# 03_BATTERY_MANAGEMENT.net
KiCad netlist of a schematic drawn in Altium Designer
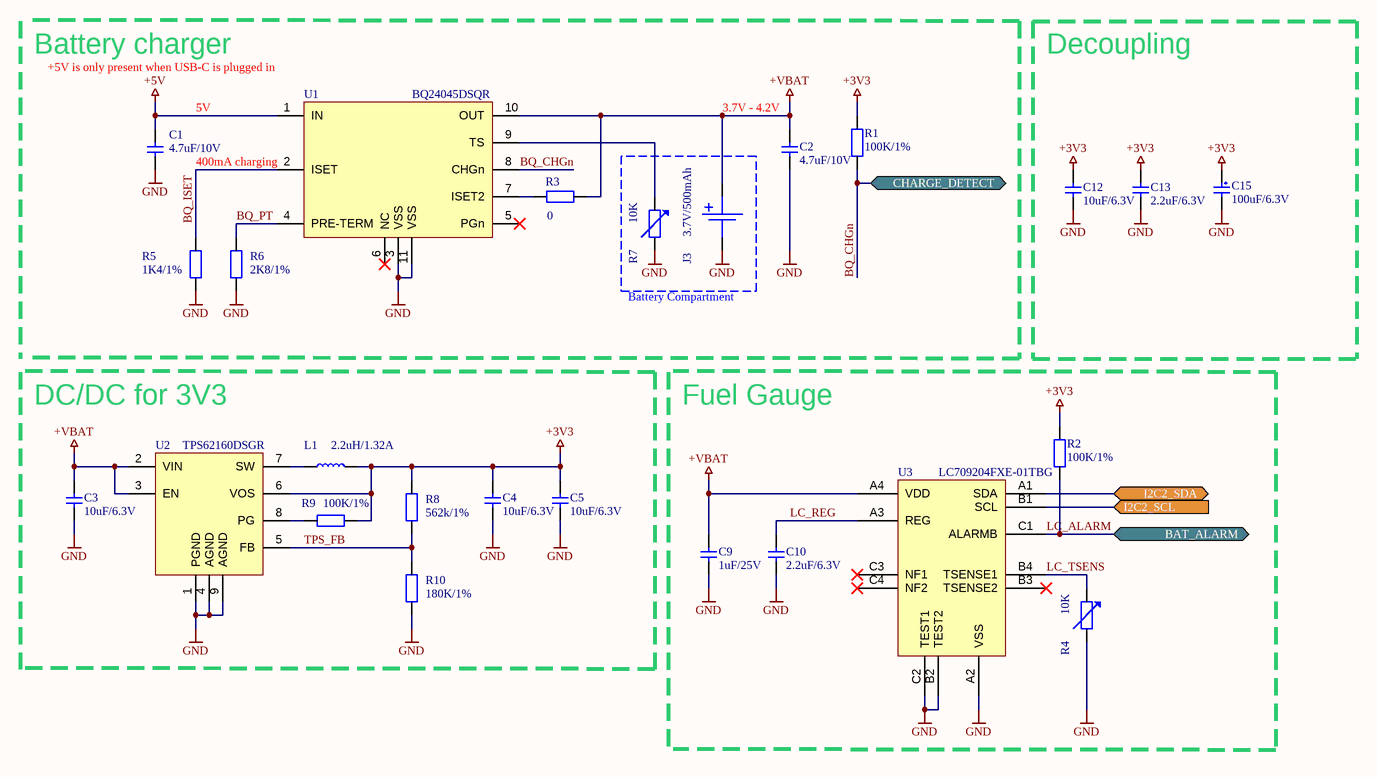
[diagram p0: 03 BATTERY MANAGEMENT.SchDoc]

(export (version "E")
  (design (tool "Eeschema 10.0.6"))
  (components
    (comp (ref "C1")
      (value "4.7uF/10V")
      (footprint "CAPC1005X06N")
      (description "10V 4.7uF X5R ±20% 0402  Multilayer Ceramic Capacitors MLCC - SMD/SMT ROHS")
      (fields
        (field (name "MANUFACTURER") "Samsung Electro-Mechanics")
        (field (name "MFR_PART_NUMBER") "CL05A475MP5NRNC")
      )
      (libsource (lib "altium_symbol") (part "CL05A475MP5NRNC"))
    )
    (comp (ref "C2")
      (value "4.7uF/10V")
      (footprint "CAPC1005X06N")
      (description "10V 4.7uF X5R ±20% 0402  Multilayer Ceramic Capacitors MLCC - SMD/SMT ROHS")
      (fields
        (field (name "MANUFACTURER") "Samsung Electro-Mechanics")
        (field (name "MFR_PART_NUMBER") "CL05A475MP5NRNC")
      )
      (libsource (lib "altium_symbol") (part "CL05A475MP5NRNC"))
    )
    (comp (ref "C3")
      (value "10uF/6.3V")
      (footprint "CAPC1005X06N")
      (description "6.3V 10uF X5R ±20% 0402  Multilayer Ceramic Capacitors MLCC - SMD/SMT ROHS")
      (fields
        (field (name "MANUFACTURER") "Samsung Electro-Mechanics")
        (field (name "MFR_PART_NUMBER") "CL05A106MQ5NUNC")
      )
      (libsource (lib "altium_symbol") (part "CL05A106MQ5NUNC"))
    )
    (comp (ref "C4")
      (value "10uF/6.3V")
      (footprint "CAPC1005X06N")
      (description "6.3V 10uF X5R ±20% 0402  Multilayer Ceramic Capacitors MLCC - SMD/SMT ROHS")
      (fields
        (field (name "MANUFACTURER") "Samsung Electro-Mechanics")
        (field (name "MFR_PART_NUMBER") "CL05A106MQ5NUNC")
      )
      (libsource (lib "altium_symbol") (part "CL05A106MQ5NUNC"))
    )
    (comp (ref "C5")
      (value "10uF/6.3V")
      (footprint "CAPC1005X06N")
      (description "6.3V 10uF X5R ±20% 0402  Multilayer Ceramic Capacitors MLCC - SMD/SMT ROHS")
      (fields
        (field (name "MANUFACTURER") "Samsung Electro-Mechanics")
        (field (name "MFR_PART_NUMBER") "CL05A106MQ5NUNC")
      )
      (libsource (lib "altium_symbol") (part "CL05A106MQ5NUNC"))
    )
    (comp (ref "C9")
      (value "1uF/25V")
      (footprint "CAPC1005X06N")
      (description "25V 1uF X5R ±10% 0402  Multilayer Ceramic Capacitors MLCC - SMD/SMT ROHS")
      (fields
        (field (name "MANUFACTURER") "Samsung Electro-Mechanics")
        (field (name "MFR_PART_NUMBER") "CL05A105KA5NQNC")
      )
      (libsource (lib "altium_symbol") (part "CL05A105KA5NQNC"))
    )
    (comp (ref "C10")
      (value "2.2uF/6.3V")
      (footprint "CAPC1005X06N")
      (description "6.3V 2.2uF X5R ±20% 0402  Multilayer Ceramic Capacitors MLCC - SMD/SMT ROHS")
      (fields
        (field (name "MANUFACTURER") "Samsung Electro-Mechanics")
        (field (name "MFR_PART_NUMBER") "CL05A225MQ5NSNC")
      )
      (libsource (lib "altium_symbol") (part "CL05A225MQ5NSNC"))
    )
    (comp (ref "C12")
      (value "10uF/6.3V")
      (footprint "CAPC1005X06N")
      (description "6.3V 10uF X5R ±20% 0402  Multilayer Ceramic Capacitors MLCC - SMD/SMT ROHS")
      (fields
        (field (name "MANUFACTURER") "Samsung Electro-Mechanics")
        (field (name "MFR_PART_NUMBER") "CL05A106MQ5NUNC")
      )
      (libsource (lib "altium_symbol") (part "CL05A106MQ5NUNC"))
    )
    (comp (ref "C13")
      (value "2.2uF/6.3V")
      (footprint "CAPC1005X06N")
      (description "6.3V 2.2uF X5R ±20% 0402  Multilayer Ceramic Capacitors MLCC - SMD/SMT ROHS")
      (fields
        (field (name "MANUFACTURER") "Samsung Electro-Mechanics")
        (field (name "MFR_PART_NUMBER") "CL05A225MQ5NSNC")
      )
      (libsource (lib "altium_symbol") (part "CL05A225MQ5NSNC"))
    )
    (comp (ref "C15")
      (value "100uF/6.3V")
      (footprint "CAPMP3528X21N")
      (description "100uF 6.3V -55℃~+125℃ 1.7Ω@100kHz ±10% CASE-B_3528 Tantalum Capacitors ROHS")
      (fields (field (name "MANUFACTURER") "Kyocera AVX") (field (name "MFR_PART_NUMBER") "TAJB107K006RNJ"))
      (libsource (lib "altium_symbol") (part "TAJB107K006RNJ"))
    )
    (comp (ref "J3")
      (value "3.7V/500mAh")
      (footprint "BATTERY_SMD_CONN")
      (description "SMD_Connector_2Pole")
      (libsource (lib "altium_symbol") (part "SMD_Connector_2Pole"))
    )
    (comp (ref "L1")
      (value "2.2uH/1.32A")
      (footprint "INDP4040X12N")
      (description "1.32A 2.2uH ±20% 104mΩ SMD  Power Inductors ROHS")
      (fields
        (field (name "MANUFACTURER") "cjiang(Changjiang Microelectronics Tech)")
        (field (name "MFR_PART_NUMBER") "FNR4012S2R2MT")
      )
      (libsource (lib "altium_symbol") (part "FNR4012S2R2MT"))
    )
    (comp (ref "R1")
      (value "100K/1%")
      (footprint "RESC1005X04N")
      (fields
        (field (name "MANUFACTURER") "UNI-ROYAL(Uniroyal Elec)")
        (field (name "MFR_PART_NUMBER") "0402WGF1003TCE")
      )
      (libsource (lib "altium_symbol") (part "0402WGF1003TCE"))
    )
    (comp (ref "R2")
      (value "100K/1%")
      (footprint "RESC1005X04N")
      (fields
        (field (name "MANUFACTURER") "UNI-ROYAL(Uniroyal Elec)")
        (field (name "MFR_PART_NUMBER") "0402WGF1003TCE")
      )
      (libsource (lib "altium_symbol") (part "0402WGF1003TCE"))
    )
    (comp (ref "R3")
      (value "0")
      (footprint "RESC1005X04N")
      (fields
        (field (name "MANUFACTURER") "UNI-ROYAL(Uniroyal Elec)")
        (field (name "MFR_PART_NUMBER") "0402WGF0000TCE")
      )
      (libsource (lib "altium_symbol") (part "0402WGF0000TCE"))
    )
    (comp (ref "R4")
      (value "10K")
      (footprint "RESC1005X04N")
      (description "10kΩ -55℃~+125℃ 0.33mA 100mW ±1% 3950K ±1% 0603  NTC Thermistors ROHS")
      (fields (field (name "MANUFACTURER") "Sunlord") (field (name "MFR_PART_NUMBER") "SDNT1608X103F3950FTF"))
      (libsource (lib "altium_symbol") (part "SDNT1608X103F3950FTF"))
    )
    (comp (ref "R5")
      (value "1K4/1%")
      (footprint "RESC1005X04N")
      (fields
        (field (name "MANUFACTURER") "UNI-ROYAL(Uniroyal Elec)")
        (field (name "MFR_PART_NUMBER") "0402WGF1401TCE")
      )
      (libsource (lib "altium_symbol") (part "0402WGF1401TCE"))
    )
    (comp (ref "R6")
      (value "2K8/1%")
      (footprint "RESC1005X04N")
      (description "62.5mW 50V ±100ppm/℃ ±1% -55℃~+155℃ 2.8kΩ 0402  Chip Resistor - Surface Mount ROHS")
      (fields
        (field (name "MANUFACTURER") "Walsin Tech Corp")
        (field (name "MFR_PART_NUMBER") "WR04X2801FTL")
      )
      (libsource (lib "altium_symbol") (part "WR04X2801FTL"))
    )
    (comp (ref "R7")
      (value "10K")
      (footprint "RESC1005X04N")
      (description "10kΩ -55℃~+125℃ 0.33mA 100mW ±1% 3950K ±1% 0603  NTC Thermistors ROHS")
      (fields (field (name "MANUFACTURER") "Sunlord") (field (name "MFR_PART_NUMBER") "SDNT1608X103F3950FTF"))
      (libsource (lib "altium_symbol") (part "SDNT1608X103F3950FTF"))
    )
    (comp (ref "R8")
      (value "562k/1%")
      (footprint "RESC1005X04N")
      (fields
        (field (name "MANUFACTURER") "UNI-ROYAL(Uniroyal Elec)")
        (field (name "MFR_PART_NUMBER") "0402WGF5623TCE")
      )
      (libsource (lib "altium_symbol") (part "0402WGF5623TCE"))
    )
    (comp (ref "R9")
      (value "100K/1%")
      (footprint "RESC1005X04N")
      (fields
        (field (name "MANUFACTURER") "UNI-ROYAL(Uniroyal Elec)")
        (field (name "MFR_PART_NUMBER") "0402WGF1003TCE")
      )
      (libsource (lib "altium_symbol") (part "0402WGF1003TCE"))
    )
    (comp (ref "R10")
      (value "180K/1%")
      (footprint "RESC1005X04N")
      (fields
        (field (name "MANUFACTURER") "UNI-ROYAL(Uniroyal Elec)")
        (field (name "MFR_PART_NUMBER") "0402WGF1803TCE")
      )
      (libsource (lib "altium_symbol") (part "0402WGF1803TCE"))
    )
    (comp (ref "U1")
      (value "BQ24045DSQR")
      (footprint "SON40P200X80_HS-11N")
      (description "WSON-10  Battery Management ICs ROHS")
      (fields (field (name "MANUFACTURER") "Texas Instruments"))
      (libsource (lib "altium_symbol") (part "BQ24045DSQR"))
    )
    (comp (ref "U2")
      (value "TPS62160DSGR")
      (footprint "SON50P200X80_HS-9N")
      (description "Step-down type WSON-8  DC-DC Converters ROHS")
      (fields (field (name "MANUFACTURER") "Texas Instruments"))
      (libsource (lib "altium_symbol") (part "TPS62160DSGR"))
    )
    (comp (ref "U3")
      (value "LC709204FXE-01TBG")
      (footprint "BGA12C40P4X3_191X148X51")
      (description "WLCSP12(1.48x1.91x0.51)  Battery Management ICs ROHS")
      (fields (field (name "MANUFACTURER") "onsemi"))
      (libsource (lib "altium_symbol") (part "LC709204FXE-01TBG"))
    )
  )
  (nets
    (net (code "1") (name "+3V3") (class "Default")
      (node (ref "C12") (pin "2") (pinfunction "2_2") (pintype "passive"))
      (node (ref "C13") (pin "2") (pinfunction "2_2") (pintype "passive"))
      (node (ref "C15") (pin "1") (pinfunction "1_1") (pintype "passive"))
      (node (ref "C4") (pin "2") (pinfunction "2_2") (pintype "passive"))
      (node (ref "C5") (pin "2") (pinfunction "2_2") (pintype "passive"))
      (node (ref "L1") (pin "2") (pinfunction "2_2") (pintype "passive"))
      (node (ref "R1") (pin "1") (pinfunction "1_1") (pintype "passive"))
      (node (ref "R2") (pin "1") (pinfunction "1_1") (pintype "passive"))
      (node (ref "R8") (pin "2") (pinfunction "2_2") (pintype "passive"))
      (node (ref "R9") (pin "1") (pinfunction "1_1") (pintype "passive"))
      (node (ref "U2") (pin "6") (pinfunction "VOS_6") (pintype "passive"))
    )
    (net (code "2") (name "+5V") (class "Default")
      (node (ref "C1") (pin "2") (pinfunction "2_2") (pintype "passive"))
      (node (ref "U1") (pin "1") (pinfunction "IN_1") (pintype "passive"))
    )
    (net (code "3") (name "+VBAT") (class "Default")
      (node (ref "C2") (pin "2") (pinfunction "2_2") (pintype "passive"))
      (node (ref "C3") (pin "2") (pinfunction "2_2") (pintype "passive"))
      (node (ref "C9") (pin "2") (pinfunction "2_2") (pintype "passive"))
      (node (ref "J3") (pin "1") (pinfunction "+_1") (pintype "passive"))
      (node (ref "R3") (pin "2") (pinfunction "2_2") (pintype "passive"))
      (node (ref "U1") (pin "10") (pinfunction "OUT_10") (pintype "passive"))
      (node (ref "U2") (pin "2") (pinfunction "VIN_2") (pintype "passive"))
      (node (ref "U2") (pin "3") (pinfunction "EN_3") (pintype "passive"))
      (node (ref "U3") (pin "A4") (pinfunction "VDD_A4") (pintype "passive"))
    )
    (net (code "4") (name "/BQ_CHGn") (class "Default")
      (node (ref "R1") (pin "2") (pinfunction "2_2") (pintype "passive"))
      (node (ref "U1") (pin "8") (pinfunction "CHGn_8") (pintype "passive"))
    )
    (net (code "5") (name "/BQ_ISET") (class "Default")
      (node (ref "R5") (pin "2") (pinfunction "2_2") (pintype "passive"))
      (node (ref "U1") (pin "2") (pinfunction "ISET_2") (pintype "passive"))
    )
    (net (code "6") (name "/BQ_PT") (class "Default")
      (node (ref "R6") (pin "2") (pinfunction "2_2") (pintype "passive"))
      (node (ref "U1") (pin "4") (pinfunction "PRE-TERM_4") (pintype "passive"))
    )
    (net (code "7") (name "/I2C2_SCL") (class "Default")
      (node (ref "U3") (pin "B1") (pinfunction "SCL_B1") (pintype "passive"))
    )
    (net (code "8") (name "/I2C2_SDA") (class "Default")
      (node (ref "U3") (pin "A1") (pinfunction "SDA_A1") (pintype "passive"))
    )
    (net (code "9") (name "/LC_ALARM") (class "Default")
      (node (ref "R2") (pin "2") (pinfunction "2_2") (pintype "passive"))
      (node (ref "U3") (pin "C1") (pinfunction "ALARMB_C1") (pintype "passive"))
    )
    (net (code "10") (name "/LC_REG") (class "Default")
      (node (ref "C10") (pin "2") (pinfunction "2_2") (pintype "passive"))
      (node (ref "U3") (pin "A3") (pinfunction "REG_A3") (pintype "passive"))
    )
    (net (code "11") (name "/LC_TSENS") (class "Default")
      (node (ref "R4") (pin "2") (pinfunction "2_2") (pintype "passive"))
      (node (ref "U3") (pin "B4") (pinfunction "TSENSE1_B4") (pintype "passive"))
    )
    (net (code "12") (name "/TPS_FB") (class "Default")
      (node (ref "R10") (pin "2") (pinfunction "2_2") (pintype "passive"))
      (node (ref "R8") (pin "1") (pinfunction "1_1") (pintype "passive"))
      (node (ref "U2") (pin "5") (pinfunction "FB_5") (pintype "passive"))
    )
    (net (code "13") (name "GND") (class "Default")
      (node (ref "C1") (pin "1") (pinfunction "1_1") (pintype "passive"))
      (node (ref "C10") (pin "1") (pinfunction "1_1") (pintype "passive"))
      (node (ref "C12") (pin "1") (pinfunction "1_1") (pintype "passive"))
      (node (ref "C13") (pin "1") (pinfunction "1_1") (pintype "passive"))
      (node (ref "C15") (pin "2") (pinfunction "2_2") (pintype "passive"))
      (node (ref "C2") (pin "1") (pinfunction "1_1") (pintype "passive"))
      (node (ref "C3") (pin "1") (pinfunction "1_1") (pintype "passive"))
      (node (ref "C4") (pin "1") (pinfunction "1_1") (pintype "passive"))
      (node (ref "C5") (pin "1") (pinfunction "1_1") (pintype "passive"))
      (node (ref "C9") (pin "1") (pinfunction "1_1") (pintype "passive"))
      (node (ref "J3") (pin "2") (pinfunction "-_2") (pintype "passive"))
      (node (ref "R10") (pin "1") (pinfunction "1_1") (pintype "passive"))
      (node (ref "R4") (pin "1") (pinfunction "1_1") (pintype "passive"))
      (node (ref "R5") (pin "1") (pinfunction "1_1") (pintype "passive"))
      (node (ref "R6") (pin "1") (pinfunction "1_1") (pintype "passive"))
      (node (ref "R7") (pin "1") (pinfunction "1_1") (pintype "passive"))
      (node (ref "U1") (pin "11") (pinfunction "VSS_11") (pintype "passive"))
      (node (ref "U1") (pin "3") (pinfunction "VSS_3") (pintype "passive"))
      (node (ref "U2") (pin "1") (pinfunction "PGND_1") (pintype "passive"))
      (node (ref "U2") (pin "4") (pinfunction "AGND_4") (pintype "passive"))
      (node (ref "U2") (pin "9") (pinfunction "AGND_9") (pintype "passive"))
      (node (ref "U3") (pin "A2") (pinfunction "VSS_A2") (pintype "passive"))
      (node (ref "U3") (pin "B2") (pinfunction "TEST2_B2") (pintype "passive"))
      (node (ref "U3") (pin "C2") (pinfunction "TEST1_C2") (pintype "passive"))
    )
    (net (code "14") (name "Net-(U1-ISET2)") (class "Default")
      (node (ref "R3") (pin "1") (pinfunction "1_1") (pintype "passive"))
      (node (ref "U1") (pin "7") (pinfunction "ISET2_7") (pintype "passive"))
    )
    (net (code "15") (name "Net-(U1-TS)") (class "Default")
      (node (ref "R7") (pin "2") (pinfunction "2_2") (pintype "passive"))
      (node (ref "U1") (pin "9") (pinfunction "TS_9") (pintype "passive"))
    )
    (net (code "16") (name "Net-(U2-PG)") (class "Default")
      (node (ref "R9") (pin "2") (pinfunction "2_2") (pintype "passive"))
      (node (ref "U2") (pin "8") (pinfunction "PG_8") (pintype "passive"))
    )
    (net (code "17") (name "Net-(U2-SW)") (class "Default")
      (node (ref "L1") (pin "1") (pinfunction "1_1") (pintype "passive"))
      (node (ref "U2") (pin "7") (pinfunction "SW_7") (pintype "passive"))
    )
    (net (code "18") (name "unconnected-(U1-NC-Pad6)") (class "Default")
      (node (ref "U1") (pin "6") (pinfunction "NC_6") (pintype "passive+no_connect"))
    )
    (net (code "19") (name "unconnected-(U1-PGn-Pad5)") (class "Default")
      (node (ref "U1") (pin "5") (pinfunction "PGn_5") (pintype "passive+no_connect"))
    )
    (net (code "20") (name "unconnected-(U3-NF1-PadC3)") (class "Default")
      (node (ref "U3") (pin "C3") (pinfunction "NF1_C3") (pintype "passive+no_connect"))
    )
    (net (code "21") (name "unconnected-(U3-NF2-PadC4)") (class "Default")
      (node (ref "U3") (pin "C4") (pinfunction "NF2_C4") (pintype "passive+no_connect"))
    )
    (net (code "22") (name "unconnected-(U3-TSENSE2-PadB3)") (class "Default")
      (node (ref "U3") (pin "B3") (pinfunction "TSENSE2_B3") (pintype "passive+no_connect"))
    )
  )
)
